# MCU.net
KiCad netlist of a schematic drawn in Altium Designer
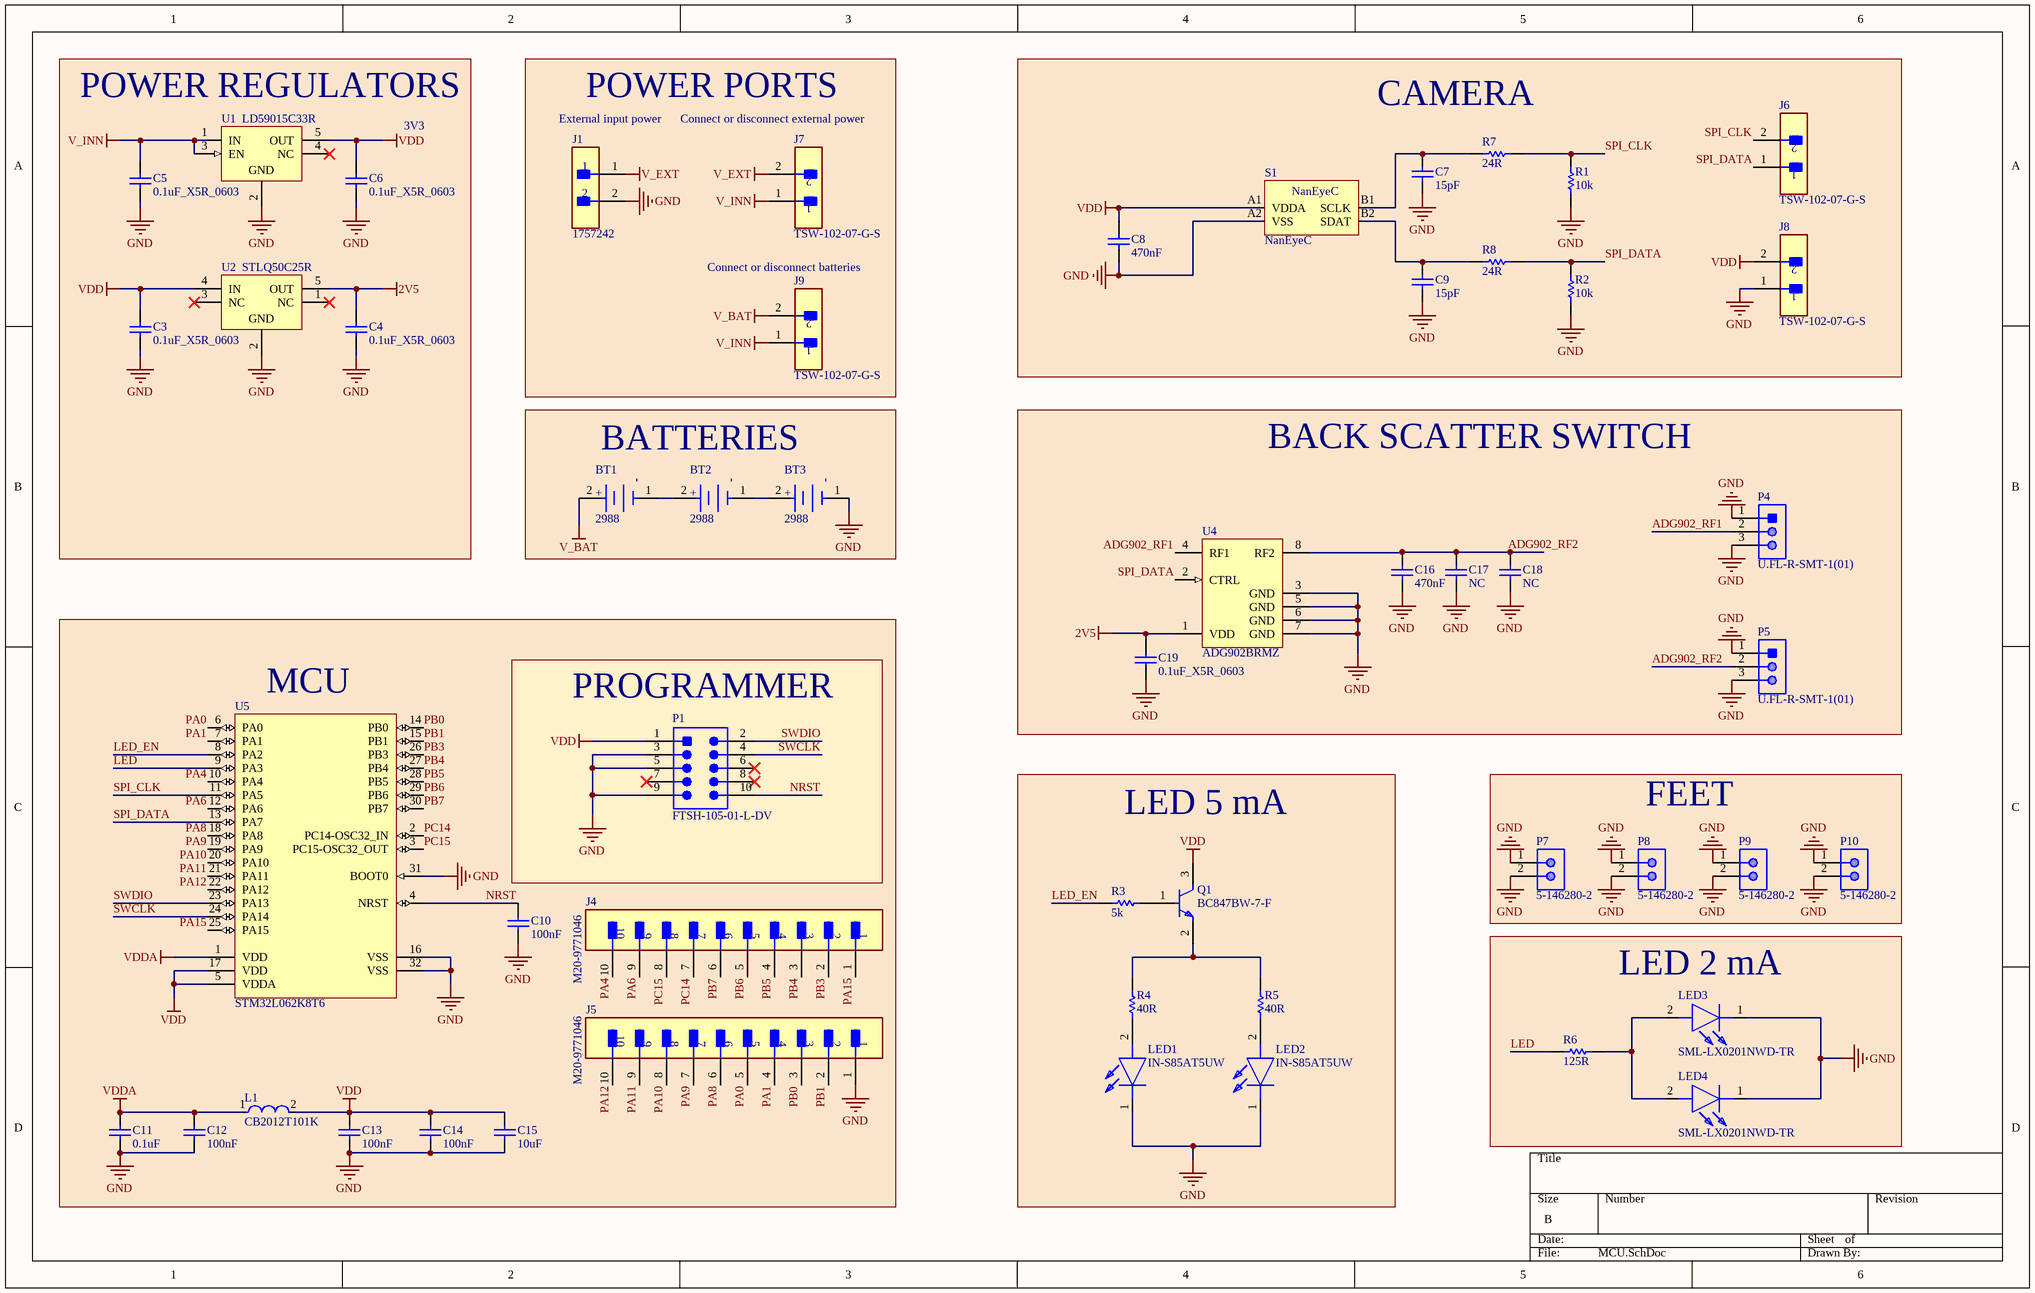
[diagram p0: MCU.SchDoc]

(export (version "E")
  (design (tool "Eeschema 10.0.6"))
  (components
    (comp (ref "BT1")
      (value "2988")
      (footprint "FP-2988-MFG")
      (description "BATTERY RETAINER COIN 7.9MM SMD")
      (libsource (lib "Altium Content Vault") (part "60d3b5b901a8747834971d0eb8cf3fd"))
    )
    (comp (ref "BT2")
      (value "2988")
      (footprint "FP-2988-MFG")
      (description "BATTERY RETAINER COIN 7.9MM SMD")
      (libsource (lib "Altium Content Vault") (part "60d3b5b901a8747834971d0eb8cf3fd"))
    )
    (comp (ref "BT3")
      (value "2988")
      (footprint "FP-2988-MFG")
      (description "BATTERY RETAINER COIN 7.9MM SMD")
      (libsource (lib "Altium Content Vault") (part "60d3b5b901a8747834971d0eb8cf3fd"))
    )
    (comp (ref "C3")
      (value "0.1uF_X5R_0603")
      (footprint "CAPC1608X90X35NL15T15")
      (fields
        (field (name "MANUFACTURER") "AVX Interconnect / Elco")
        (field (name "PART NUMBER") "06035D104KAT2A")
      )
      (libsource (lib "Altium Content Vault") (part "CAP"))
    )
    (comp (ref "C4")
      (value "0.1uF_X5R_0603")
      (footprint "CAPC1608X90X35NL15T15")
      (fields
        (field (name "MANUFACTURER") "AVX Interconnect / Elco")
        (field (name "PART NUMBER") "06035D104KAT2A")
      )
      (libsource (lib "Altium Content Vault") (part "CAP"))
    )
    (comp (ref "C5")
      (value "0.1uF_X5R_0603")
      (footprint "CAPC1608X90X35NL15T15")
      (fields
        (field (name "MANUFACTURER") "AVX Interconnect / Elco")
        (field (name "PART NUMBER") "06035D104KAT2A")
      )
      (libsource (lib "Altium Content Vault") (part "CAP"))
    )
    (comp (ref "C6")
      (value "0.1uF_X5R_0603")
      (footprint "CAPC1608X90X35NL15T15")
      (fields
        (field (name "MANUFACTURER") "AVX Interconnect / Elco")
        (field (name "PART NUMBER") "06035D104KAT2A")
      )
      (libsource (lib "Altium Content Vault") (part "CAP"))
    )
    (comp (ref "C7")
      (value "15pF")
      (footprint "CAPC1608X90X35NL15T15")
      (fields
        (field (name "MANUFACTURER") "AVX Interconnect / Elco")
        (field (name "PART NUMBER") "06035D104KAT2A")
      )
      (libsource (lib "Altium Content Vault") (part "CAP"))
    )
    (comp (ref "C8")
      (value "470nF")
      (footprint "CAPC1608X90X35NL15T15")
      (fields
        (field (name "MANUFACTURER") "AVX Interconnect / Elco")
        (field (name "PART NUMBER") "06035D104KAT2A")
      )
      (libsource (lib "Altium Content Vault") (part "CAP"))
    )
    (comp (ref "C9")
      (value "15pF")
      (footprint "CAPC1608X90X35NL15T15")
      (fields
        (field (name "MANUFACTURER") "AVX Interconnect / Elco")
        (field (name "PART NUMBER") "06035D104KAT2A")
      )
      (libsource (lib "Altium Content Vault") (part "CAP"))
    )
    (comp (ref "C10")
      (value "100nF")
      (footprint "CAPC1608X90X35NL15T15")
      (fields
        (field (name "MANUFACTURER") "AVX Interconnect / Elco")
        (field (name "PART NUMBER") "06035D104KAT2A")
      )
      (libsource (lib "Altium Content Vault") (part "CAP"))
    )
    (comp (ref "C11")
      (value "0.1uF")
      (footprint "CAPC1608X90X35NL15T15")
      (fields
        (field (name "MANUFACTURER") "AVX Interconnect / Elco")
        (field (name "PART NUMBER") "06035D104KAT2A")
      )
      (libsource (lib "Altium Content Vault") (part "CAP"))
    )
    (comp (ref "C12")
      (value "100nF")
      (footprint "CAPC1608X90X35NL15T15")
      (fields
        (field (name "MANUFACTURER") "AVX Interconnect / Elco")
        (field (name "PART NUMBER") "06035D104KAT2A")
      )
      (libsource (lib "Altium Content Vault") (part "CAP"))
    )
    (comp (ref "C13")
      (value "100nF")
      (footprint "CAPC1608X90X35NL15T15")
      (fields
        (field (name "MANUFACTURER") "AVX Interconnect / Elco")
        (field (name "PART NUMBER") "06035D104KAT2A")
      )
      (libsource (lib "Altium Content Vault") (part "CAP"))
    )
    (comp (ref "C14")
      (value "100nF")
      (footprint "CAPC1608X90X35NL15T15")
      (fields
        (field (name "MANUFACTURER") "AVX Interconnect / Elco")
        (field (name "PART NUMBER") "06035D104KAT2A")
      )
      (libsource (lib "Altium Content Vault") (part "CAP"))
    )
    (comp (ref "C15")
      (value "10uF")
      (footprint "CAPC1608X90X35NL15T15")
      (fields
        (field (name "MANUFACTURER") "AVX Interconnect / Elco")
        (field (name "PART NUMBER") "06035D104KAT2A")
      )
      (libsource (lib "Altium Content Vault") (part "CAP"))
    )
    (comp (ref "C16")
      (value "470nF")
      (footprint "CAPC1608X90X35NL15T15")
      (fields
        (field (name "MANUFACTURER") "AVX Interconnect / Elco")
        (field (name "PART NUMBER") "06035D104KAT2A")
      )
      (libsource (lib "Altium Content Vault") (part "CAP"))
    )
    (comp (ref "C17")
      (value "NC")
      (footprint "CAPC1608X90X35NL15T15")
      (fields
        (field (name "MANUFACTURER") "AVX Interconnect / Elco")
        (field (name "PART NUMBER") "06035D104KAT2A")
      )
      (libsource (lib "Altium Content Vault") (part "CAP"))
    )
    (comp (ref "C18")
      (value "NC")
      (footprint "CAPC1608X90X35NL15T15")
      (fields
        (field (name "MANUFACTURER") "AVX Interconnect / Elco")
        (field (name "PART NUMBER") "06035D104KAT2A")
      )
      (libsource (lib "Altium Content Vault") (part "CAP"))
    )
    (comp (ref "C19")
      (value "0.1uF_X5R_0603")
      (footprint "CAPC1608X90X35NL15T15")
      (fields
        (field (name "MANUFACTURER") "AVX Interconnect / Elco")
        (field (name "PART NUMBER") "06035D104KAT2A")
      )
      (libsource (lib "Altium Content Vault") (part "CAP"))
    )
    (comp (ref "J1")
      (value "1757242")
      (footprint "FP-1757242-MFG")
      (description "TERM BLOCK HDR 2POS 90DEG 5.08MM")
      (fields (field (name "VOLTAGE") "300V"))
      (libsource (lib "Altium Content Vault") (part "3bc925449376181038e59eaffc5286c"))
    )
    (comp (ref "J4")
      (value "M20-9771046")
      (footprint "FP-M20-9771046-MFG")
      (description "CONN HEADER VERT 10POS 2.54MM")
      (libsource (lib "Altium Content Vault") (part "aee40dc8b284c03a16094555aa210be"))
    )
    (comp (ref "J5")
      (value "M20-9771046")
      (footprint "FP-M20-9771046-MFG")
      (description "CONN HEADER VERT 10POS 2.54MM")
      (libsource (lib "Altium Content Vault") (part "aee40dc8b284c03a16094555aa210be"))
    )
    (comp (ref "J6")
      (value "TSW-102-07-G-S")
      (footprint "FP-TSW-102-07-G-S-MFG")
      (description "CONN HEADER VERT 2POS 2.54MM")
      (fields
        (field (name "MANUFACTURER") "Samtec")
        (field (name "OCTOPART") "https://octopart.com/tsw-102-07-g-s-samtec-272197")
      )
      (libsource (lib "") (part "3bc925449376181038e59eaffc5286c_1"))
    )
    (comp (ref "J7")
      (value "TSW-102-07-G-S")
      (footprint "FP-TSW-102-07-G-S-MFG")
      (description "CONN HEADER VERT 2POS 2.54MM")
      (fields
        (field (name "MANUFACTURER") "Samtec")
        (field (name "OCTOPART") "https://octopart.com/tsw-102-07-g-s-samtec-272197")
      )
      (libsource (lib "") (part "3bc925449376181038e59eaffc5286c_1"))
    )
    (comp (ref "J8")
      (value "TSW-102-07-G-S")
      (footprint "FP-TSW-102-07-G-S-MFG")
      (description "CONN HEADER VERT 2POS 2.54MM")
      (fields
        (field (name "MANUFACTURER") "Samtec")
        (field (name "OCTOPART") "https://octopart.com/tsw-102-07-g-s-samtec-272197")
      )
      (libsource (lib "") (part "3bc925449376181038e59eaffc5286c_1"))
    )
    (comp (ref "J9")
      (value "TSW-102-07-G-S")
      (footprint "FP-TSW-102-07-G-S-MFG")
      (description "CONN HEADER VERT 2POS 2.54MM")
      (fields
        (field (name "MANUFACTURER") "Samtec")
        (field (name "OCTOPART") "https://octopart.com/tsw-102-07-g-s-samtec-272197")
      )
      (libsource (lib "") (part "3bc925449376181038e59eaffc5286c_1"))
    )
    (comp (ref "L1")
      (value "CB2012T101K")
      (footprint "FP-CB2012-MFG")
      (description "SMD Inductors 100uH ±10% 0.13A 9.1Ω 0805")
      (fields (field (name "TOLERANCE") "10%"))
      (libsource (lib "Altium Content Vault") (part "725321dda6339637d4d059423bc1c3c"))
    )
    (comp (ref "LED1")
      (value "IN-S85AT5UW")
      (footprint "SamacSys:INS85AT5UW")
      (description "LED")
      (fields (field (name "MOUSER PART NUMBER") "743-IN-S85AT5UW"))
      (libsource (lib "*") (part "IN-S85AT5UW"))
    )
    (comp (ref "LED2")
      (value "IN-S85AT5UW")
      (footprint "SamacSys:INS85AT5UW")
      (description "LED")
      (fields (field (name "MOUSER PART NUMBER") "743-IN-S85AT5UW"))
      (libsource (lib "SamacSys") (part "IN-S85AT5UW"))
    )
    (comp (ref "LED3")
      (value "SML-LX0201NWD-TR")
      (footprint "SamacSys:LEDC0604X46N")
      (description "LED")
      (fields (field (name "MOUSER2 PART NUMBER") "696-SMLLX0201NWDTR"))
      (libsource (lib "*") (part "SML-LX0201NWD-TR"))
    )
    (comp (ref "LED4")
      (value "SML-LX0201NWD-TR")
      (footprint "SamacSys:LEDC0604X46N")
      (description "LED")
      (fields (field (name "MOUSER2 PART NUMBER") "696-SMLLX0201NWDTR"))
      (libsource (lib "*") (part "SML-LX0201NWD-TR"))
    )
    (comp (ref "P1")
      (value "FTSH-105-01-L-DV")
      (footprint "SMTC-FTSH-105-01-L-DV_V")
      (description "Male Header, Pitch 1.27 mm, 2 x 5 Position, Height 5.96 mm, -55 to 125 degC, RoHS, Bulk")
      (fields (field (name "MANUFACTURER") "Samtec"))
      (libsource (lib "Altium Content Vault") (part "CN-2P-M-R10"))
    )
    (comp (ref "P4")
      (value "U.FL-R-SMT-1(01)")
      (footprint "HRS-U.FL-R-SMT-3_V")
      (description "Ultra Small Coaxial Connector, 6 GHz, -40 to 90 degC, 3-Pin SMD, RoHS, Bulk")
      (fields (field (name "MANUFACTURER") "Hirose Electric"))
      (libsource (lib "Altium Content Vault") (part "CN-1P-M-R3"))
    )
    (comp (ref "P5")
      (value "U.FL-R-SMT-1(01)")
      (footprint "HRS-U.FL-R-SMT-3_V")
      (description "Ultra Small Coaxial Connector, 6 GHz, -40 to 90 degC, 3-Pin SMD, RoHS, Bulk")
      (fields (field (name "MANUFACTURER") "Hirose Electric"))
      (libsource (lib "Altium Content Vault") (part "CN-1P-M-R3"))
    )
    (comp (ref "P7")
      (value "5-146280-2")
      (footprint "TECO-5-146280-2_V")
      (fields (field (name "MANUFACTURER") "TE Connectivity"))
      (libsource (lib "Altium Content Vault") (part "CN-1P-M-R2"))
    )
    (comp (ref "P8")
      (value "5-146280-2")
      (footprint "TECO-5-146280-2_V")
      (fields (field (name "MANUFACTURER") "TE Connectivity"))
      (libsource (lib "Altium Content Vault") (part "CN-1P-M-R2"))
    )
    (comp (ref "P9")
      (value "5-146280-2")
      (footprint "TECO-5-146280-2_V")
      (fields (field (name "MANUFACTURER") "TE Connectivity"))
      (libsource (lib "Altium Content Vault") (part "CN-1P-M-R2"))
    )
    (comp (ref "P10")
      (value "5-146280-2")
      (footprint "TECO-5-146280-2_V")
      (fields (field (name "MANUFACTURER") "TE Connectivity"))
      (libsource (lib "Altium Content Vault") (part "CN-1P-M-R2"))
    )
    (comp (ref "Q1")
      (value "BC847BW-7-F")
      (footprint "FP-SOT323-MFG")
      (description "TRANS NPN 45V 0.1A SC70-3")
      (fields
        (field (name "OCTOPART") "https://octopart.com/bc847bw-7-f-diodes+inc.-354380")
        (field (name "MANUFACTURER") "Diodes Inc")
      )
      (libsource (lib "Altium Content Vault") (part "b44e953556f554d0102664c7d152cb4"))
    )
    (comp (ref "R1")
      (value "10k")
      (footprint "RESC1608X50X30ML20T20")
      (fields (field (name "PART NUMBER") "RR0816P-4640-D-65A") (field (name "MANUFACTURER") "Susumu"))
      (libsource (lib "Altium Content Vault") (part "RES"))
    )
    (comp (ref "R2")
      (value "10k")
      (footprint "RESC1608X50X30ML20T20")
      (fields (field (name "PART NUMBER") "RR0816P-4640-D-65A") (field (name "MANUFACTURER") "Susumu"))
      (libsource (lib "Altium Content Vault") (part "RES"))
    )
    (comp (ref "R3")
      (value "5k")
      (footprint "RESC1608X50X30ML20T20")
      (fields (field (name "PART NUMBER") "RR0816P-4640-D-65A") (field (name "MANUFACTURER") "Susumu"))
      (libsource (lib "Altium Content Vault") (part "RES"))
    )
    (comp (ref "R4")
      (value "40R")
      (footprint "RESC1608X50X30ML20T20")
      (fields (field (name "PART NUMBER") "RR0816P-4640-D-65A") (field (name "MANUFACTURER") "Susumu"))
      (libsource (lib "Altium Content Vault") (part "RES"))
    )
    (comp (ref "R5")
      (value "40R")
      (footprint "RESC1608X50X30ML20T20")
      (fields (field (name "PART NUMBER") "RR0816P-4640-D-65A") (field (name "MANUFACTURER") "Susumu"))
      (libsource (lib "Altium Content Vault") (part "RES"))
    )
    (comp (ref "R6")
      (value "125R")
      (footprint "RESC1608X50X30ML20T20")
      (fields (field (name "PART NUMBER") "RR0816P-4640-D-65A") (field (name "MANUFACTURER") "Susumu"))
      (libsource (lib "Altium Content Vault") (part "RES"))
    )
    (comp (ref "R7")
      (value "24R")
      (footprint "RESC1608X50X30ML20T20")
      (fields (field (name "PART NUMBER") "RR0816P-4640-D-65A") (field (name "MANUFACTURER") "Susumu"))
      (libsource (lib "Altium Content Vault") (part "RES"))
    )
    (comp (ref "R8")
      (value "24R")
      (footprint "RESC1608X50X30ML20T20")
      (fields (field (name "PART NUMBER") "RR0816P-4640-D-65A") (field (name "MANUFACTURER") "Susumu"))
      (libsource (lib "Altium Content Vault") (part "RES"))
    )
    (comp (ref "S1")
      (value "NanEyeC")
      (footprint "NanEyeC")
      (description "Camera module NanEyeC from AMS. The Part will be delivered by us")
      (libsource (lib "WCE_thesis") (part "NanEyeC"))
    )
    (comp (ref "U1")
      (value "LD59015C33R")
      (footprint "SOT323-5L-L036_L")
      (description "150 mA Low Noise High PSRR linear Voltage Regulator, 3.3V, 5-Pin SOT-323, Tape and Reel")
      (libsource (lib "Altium Content Vault") (part "PM-REG-LD39015M-SOT5"))
    )
    (comp (ref "U2")
      (value "STLQ50C25R")
      (footprint "SOT323-5L_L")
      (description "50mA, 3µA Supply Current Low Drop Linear Regulator, 2.5V, 5-Pin SOT-323, Tape and Reel")
      (libsource (lib "Altium Content Vault") (part "PM-REG-STLQ50C-SOT5"))
    )
    (comp (ref "U4")
      (value "ADG902BRMZ")
      (footprint "ADI-RM-8_L")
      (libsource (lib "Altium Content Vault") (part "ADI-ADG902-RM-8"))
    )
    (comp (ref "U5")
      (value "STM32L062K8T6")
      (footprint "STM-LQFP32_M")
      (libsource (lib "Altium Content Vault") (part "MC-ARM-STM32L062-LQFP32"))
    )
  )
  (nets
    (net (code "2") (name "/ADG902_RF1") (class "Default")
      (node (ref "P4") (pin "2") (pinfunction "2_2") (pintype "passive"))
      (node (ref "U4") (pin "4") (pinfunction "RF1_4") (pintype "passive"))
    )
    (net (code "3") (name "/ADG902_RF2") (class "Default")
      (node (ref "C16") (pin "2") (pinfunction "2_2") (pintype "passive"))
      (node (ref "C17") (pin "2") (pinfunction "2_2") (pintype "passive"))
      (node (ref "C18") (pin "2") (pinfunction "2_2") (pintype "passive"))
      (node (ref "P5") (pin "2") (pinfunction "2_2") (pintype "passive"))
      (node (ref "U4") (pin "8") (pinfunction "RF2_8") (pintype "passive"))
    )
    (net (code "4") (name "/LED") (class "Default")
      (node (ref "R6") (pin "2") (pinfunction "2_2") (pintype "passive"))
      (node (ref "U5") (pin "9") (pinfunction "PA3_9") (pintype "bidirectional"))
    )
    (net (code "5") (name "/LED_EN") (class "Default")
      (node (ref "R3") (pin "2") (pinfunction "2_2") (pintype "passive"))
      (node (ref "U5") (pin "8") (pinfunction "PA2_8") (pintype "bidirectional"))
    )
    (net (code "6") (name "/NRST") (class "Default")
      (node (ref "C10") (pin "2") (pinfunction "2_2") (pintype "passive"))
      (node (ref "P1") (pin "10") (pinfunction "10_10") (pintype "passive"))
      (node (ref "U5") (pin "4") (pinfunction "NRST_4") (pintype "bidirectional"))
    )
    (net (code "7") (name "/PA0") (class "Default")
      (node (ref "J5") (pin "5") (pinfunction "5_5") (pintype "passive"))
      (node (ref "U5") (pin "6") (pinfunction "PA0_6") (pintype "bidirectional"))
    )
    (net (code "8") (name "/PA1") (class "Default")
      (node (ref "J5") (pin "4") (pinfunction "4_4") (pintype "passive"))
      (node (ref "U5") (pin "7") (pinfunction "PA1_7") (pintype "bidirectional"))
    )
    (net (code "9") (name "/PA4") (class "Default")
      (node (ref "J4") (pin "10") (pinfunction "10_10") (pintype "passive"))
      (node (ref "U5") (pin "10") (pinfunction "PA4_10") (pintype "bidirectional"))
    )
    (net (code "10") (name "/PA6") (class "Default")
      (node (ref "J4") (pin "9") (pinfunction "9_9") (pintype "passive"))
      (node (ref "U5") (pin "12") (pinfunction "PA6_12") (pintype "bidirectional"))
    )
    (net (code "11") (name "/PA8") (class "Default")
      (node (ref "J5") (pin "6") (pinfunction "6_6") (pintype "passive"))
      (node (ref "U5") (pin "18") (pinfunction "PA8_18") (pintype "bidirectional"))
    )
    (net (code "12") (name "/PA9") (class "Default")
      (node (ref "J5") (pin "7") (pinfunction "7_7") (pintype "passive"))
      (node (ref "U5") (pin "19") (pinfunction "PA9_19") (pintype "bidirectional"))
    )
    (net (code "13") (name "/PA10") (class "Default")
      (node (ref "J5") (pin "8") (pinfunction "8_8") (pintype "passive"))
      (node (ref "U5") (pin "20") (pinfunction "PA10_20") (pintype "bidirectional"))
    )
    (net (code "14") (name "/PA11") (class "Default")
      (node (ref "J5") (pin "9") (pinfunction "9_9") (pintype "passive"))
      (node (ref "U5") (pin "21") (pinfunction "PA11_21") (pintype "bidirectional"))
    )
    (net (code "15") (name "/PA12") (class "Default")
      (node (ref "J5") (pin "10") (pinfunction "10_10") (pintype "passive"))
      (node (ref "U5") (pin "22") (pinfunction "PA12_22") (pintype "bidirectional"))
    )
    (net (code "16") (name "/PA15") (class "Default")
      (node (ref "J4") (pin "1") (pinfunction "1_1") (pintype "passive"))
      (node (ref "U5") (pin "25") (pinfunction "PA15_25") (pintype "bidirectional"))
    )
    (net (code "17") (name "/PB0") (class "Default")
      (node (ref "J5") (pin "3") (pinfunction "3_3") (pintype "passive"))
      (node (ref "U5") (pin "14") (pinfunction "PB0_14") (pintype "bidirectional"))
    )
    (net (code "18") (name "/PB1") (class "Default")
      (node (ref "J5") (pin "2") (pinfunction "2_2") (pintype "passive"))
      (node (ref "U5") (pin "15") (pinfunction "PB1_15") (pintype "bidirectional"))
    )
    (net (code "19") (name "/PB3") (class "Default")
      (node (ref "J4") (pin "2") (pinfunction "2_2") (pintype "passive"))
      (node (ref "U5") (pin "26") (pinfunction "PB3_26") (pintype "bidirectional"))
    )
    (net (code "20") (name "/PB4") (class "Default")
      (node (ref "J4") (pin "3") (pinfunction "3_3") (pintype "passive"))
      (node (ref "U5") (pin "27") (pinfunction "PB4_27") (pintype "bidirectional"))
    )
    (net (code "21") (name "/PB5") (class "Default")
      (node (ref "J4") (pin "4") (pinfunction "4_4") (pintype "passive"))
      (node (ref "U5") (pin "28") (pinfunction "PB5_28") (pintype "bidirectional"))
    )
    (net (code "22") (name "/PB6") (class "Default")
      (node (ref "J4") (pin "5") (pinfunction "5_5") (pintype "passive"))
      (node (ref "U5") (pin "29") (pinfunction "PB6_29") (pintype "bidirectional"))
    )
    (net (code "23") (name "/PB7") (class "Default")
      (node (ref "J4") (pin "6") (pinfunction "6_6") (pintype "passive"))
      (node (ref "U5") (pin "30") (pinfunction "PB7_30") (pintype "bidirectional"))
    )
    (net (code "24") (name "/PC14") (class "Default")
      (node (ref "J4") (pin "7") (pinfunction "7_7") (pintype "passive"))
      (node (ref "U5") (pin "2") (pinfunction "PC14-OSC32_IN_2") (pintype "bidirectional"))
    )
    (net (code "25") (name "/PC15") (class "Default")
      (node (ref "J4") (pin "8") (pinfunction "8_8") (pintype "passive"))
      (node (ref "U5") (pin "3") (pinfunction "PC15-OSC32_OUT_3") (pintype "bidirectional"))
    )
    (net (code "26") (name "/SPI_CLK") (class "Default")
      (node (ref "J6") (pin "2") (pinfunction "2_2") (pintype "passive"))
      (node (ref "R1") (pin "2") (pinfunction "2_2") (pintype "passive"))
      (node (ref "R7") (pin "1") (pinfunction "1_1") (pintype "passive"))
      (node (ref "U5") (pin "11") (pinfunction "PA5_11") (pintype "bidirectional"))
    )
    (net (code "27") (name "/SPI_DATA") (class "Default")
      (node (ref "J6") (pin "1") (pinfunction "1_1") (pintype "passive"))
      (node (ref "R2") (pin "2") (pinfunction "2_2") (pintype "passive"))
      (node (ref "R8") (pin "1") (pinfunction "1_1") (pintype "passive"))
      (node (ref "U4") (pin "2") (pinfunction "CTRL_2") (pintype "input"))
      (node (ref "U5") (pin "13") (pinfunction "PA7_13") (pintype "bidirectional"))
    )
    (net (code "28") (name "/SWCLK") (class "Default")
      (node (ref "P1") (pin "4") (pinfunction "4_4") (pintype "passive"))
      (node (ref "U5") (pin "24") (pinfunction "PA14_24") (pintype "bidirectional"))
    )
    (net (code "29") (name "/SWDIO") (class "Default")
      (node (ref "P1") (pin "2") (pinfunction "2_2") (pintype "passive"))
      (node (ref "U5") (pin "23") (pinfunction "PA13_23") (pintype "bidirectional"))
    )
    (net (code "30") (name "2V5") (class "Default")
      (node (ref "C19") (pin "2") (pinfunction "2_2") (pintype "passive"))
      (node (ref "C4") (pin "2") (pinfunction "2_2") (pintype "passive"))
      (node (ref "U2") (pin "5") (pinfunction "OUT_5") (pintype "power_in"))
      (node (ref "U4") (pin "1") (pinfunction "VDD_1") (pintype "power_in"))
    )
    (net (code "31") (name "GND") (class "Default")
      (node (ref "BT3") (pin "1") (pinfunction "C_1") (pintype "passive"))
      (node (ref "C10") (pin "1") (pinfunction "1_1") (pintype "passive"))
      (node (ref "C11") (pin "1") (pinfunction "1_1") (pintype "passive"))
      (node (ref "C12") (pin "1") (pinfunction "1_1") (pintype "passive"))
      (node (ref "C13") (pin "1") (pinfunction "1_1") (pintype "passive"))
      (node (ref "C14") (pin "1") (pinfunction "1_1") (pintype "passive"))
      (node (ref "C15") (pin "1") (pinfunction "1_1") (pintype "passive"))
      (node (ref "C16") (pin "1") (pinfunction "1_1") (pintype "passive"))
      (node (ref "C17") (pin "1") (pinfunction "1_1") (pintype "passive"))
      (node (ref "C18") (pin "1") (pinfunction "1_1") (pintype "passive"))
      (node (ref "C19") (pin "1") (pinfunction "1_1") (pintype "passive"))
      (node (ref "C3") (pin "1") (pinfunction "1_1") (pintype "passive"))
      (node (ref "C4") (pin "1") (pinfunction "1_1") (pintype "passive"))
      (node (ref "C5") (pin "1") (pinfunction "1_1") (pintype "passive"))
      (node (ref "C6") (pin "1") (pinfunction "1_1") (pintype "passive"))
      (node (ref "C7") (pin "1") (pinfunction "1_1") (pintype "passive"))
      (node (ref "C8") (pin "1") (pinfunction "1_1") (pintype "passive"))
      (node (ref "C9") (pin "1") (pinfunction "1_1") (pintype "passive"))
      (node (ref "J1") (pin "2") (pinfunction "2_2") (pintype "passive"))
      (node (ref "J5") (pin "1") (pinfunction "1_1") (pintype "passive"))
      (node (ref "J8") (pin "1") (pinfunction "1_1") (pintype "passive"))
      (node (ref "LED1") (pin "1") (pinfunction "K_1") (pintype "passive"))
      (node (ref "LED2") (pin "1") (pinfunction "K_1") (pintype "passive"))
      (node (ref "LED3") (pin "1") (pinfunction "K_1") (pintype "passive"))
      (node (ref "LED4") (pin "1") (pinfunction "K_1") (pintype "passive"))
      (node (ref "P1") (pin "3") (pinfunction "3_3") (pintype "passive"))
      (node (ref "P1") (pin "5") (pinfunction "5_5") (pintype "passive"))
      (node (ref "P1") (pin "9") (pinfunction "9_9") (pintype "passive"))
      (node (ref "P10") (pin "1") (pinfunction "1_1") (pintype "passive"))
      (node (ref "P10") (pin "2") (pinfunction "2_2") (pintype "passive"))
      (node (ref "P4") (pin "1") (pinfunction "1_1") (pintype "passive"))
      (node (ref "P4") (pin "3") (pinfunction "3_3") (pintype "passive"))
      (node (ref "P5") (pin "1") (pinfunction "1_1") (pintype "passive"))
      (node (ref "P5") (pin "3") (pinfunction "3_3") (pintype "passive"))
      (node (ref "P7") (pin "1") (pinfunction "1_1") (pintype "passive"))
      (node (ref "P7") (pin "2") (pinfunction "2_2") (pintype "passive"))
      (node (ref "P8") (pin "1") (pinfunction "1_1") (pintype "passive"))
      (node (ref "P8") (pin "2") (pinfunction "2_2") (pintype "passive"))
      (node (ref "P9") (pin "1") (pinfunction "1_1") (pintype "passive"))
      (node (ref "P9") (pin "2") (pinfunction "2_2") (pintype "passive"))
      (node (ref "R1") (pin "1") (pinfunction "1_1") (pintype "passive"))
      (node (ref "R2") (pin "1") (pinfunction "1_1") (pintype "passive"))
      (node (ref "S1") (pin "A2") (pinfunction "VSS_A2") (pintype "passive"))
      (node (ref "U1") (pin "2") (pinfunction "GND_2") (pintype "power_in"))
      (node (ref "U2") (pin "2") (pinfunction "GND_2") (pintype "power_in"))
      (node (ref "U4") (pin "3") (pinfunction "GND_3") (pintype "power_in"))
      (node (ref "U4") (pin "5") (pinfunction "GND_5") (pintype "power_in"))
      (node (ref "U4") (pin "6") (pinfunction "GND_6") (pintype "power_in"))
      (node (ref "U4") (pin "7") (pinfunction "GND_7") (pintype "power_in"))
      (node (ref "U5") (pin "16") (pinfunction "VSS_16") (pintype "power_in"))
      (node (ref "U5") (pin "31") (pinfunction "BOOT0_31") (pintype "input"))
      (node (ref "U5") (pin "32") (pinfunction "VSS_32") (pintype "power_in"))
    )
    (net (code "32") (name "Net-(BT1-C)") (class "Default")
      (node (ref "BT1") (pin "1") (pinfunction "C_1") (pintype "passive"))
      (node (ref "BT2") (pin "2") (pinfunction "A_2") (pintype "passive"))
    )
    (net (code "33") (name "Net-(BT2-C)") (class "Default")
      (node (ref "BT2") (pin "1") (pinfunction "C_1") (pintype "passive"))
      (node (ref "BT3") (pin "2") (pinfunction "A_2") (pintype "passive"))
    )
    (net (code "34") (name "Net-(LED1-A)") (class "Default")
      (node (ref "LED1") (pin "2") (pinfunction "A_2") (pintype "passive"))
      (node (ref "R4") (pin "1") (pinfunction "1_1") (pintype "passive"))
    )
    (net (code "35") (name "Net-(LED2-A)") (class "Default")
      (node (ref "LED2") (pin "2") (pinfunction "A_2") (pintype "passive"))
      (node (ref "R5") (pin "1") (pinfunction "1_1") (pintype "passive"))
    )
    (net (code "36") (name "Net-(LED3-A)") (class "Default")
      (node (ref "LED3") (pin "2") (pinfunction "A_2") (pintype "passive"))
      (node (ref "LED4") (pin "2") (pinfunction "A_2") (pintype "passive"))
      (node (ref "R6") (pin "1") (pinfunction "1_1") (pintype "passive"))
    )
    (net (code "37") (name "Net-(Q1-B)") (class "Default")
      (node (ref "Q1") (pin "1") (pinfunction "B_1") (pintype "passive"))
      (node (ref "R3") (pin "1") (pinfunction "1_1") (pintype "passive"))
    )
    (net (code "38") (name "Net-(Q1-E)") (class "Default")
      (node (ref "Q1") (pin "2") (pinfunction "E_2") (pintype "passive"))
      (node (ref "R4") (pin "2") (pinfunction "2_2") (pintype "passive"))
      (node (ref "R5") (pin "2") (pinfunction "2_2") (pintype "passive"))
    )
    (net (code "39") (name "Net-(S1-SCLK)") (class "Default")
      (node (ref "C7") (pin "2") (pinfunction "2_2") (pintype "passive"))
      (node (ref "R7") (pin "2") (pinfunction "2_2") (pintype "passive"))
      (node (ref "S1") (pin "B1") (pinfunction "SCLK_B1") (pintype "power_in"))
    )
    (net (code "40") (name "Net-(S1-SDAT)") (class "Default")
      (node (ref "C9") (pin "2") (pinfunction "2_2") (pintype "passive"))
      (node (ref "R8") (pin "2") (pinfunction "2_2") (pintype "passive"))
      (node (ref "S1") (pin "B2") (pinfunction "SDAT_B2") (pintype "passive"))
    )
    (net (code "41") (name "VDD") (class "Default")
      (node (ref "C13") (pin "2") (pinfunction "2_2") (pintype "passive"))
      (node (ref "C14") (pin "2") (pinfunction "2_2") (pintype "passive"))
      (node (ref "C15") (pin "2") (pinfunction "2_2") (pintype "passive"))
      (node (ref "C3") (pin "2") (pinfunction "2_2") (pintype "passive"))
      (node (ref "C6") (pin "2") (pinfunction "2_2") (pintype "passive"))
      (node (ref "C8") (pin "2") (pinfunction "2_2") (pintype "passive"))
      (node (ref "J8") (pin "2") (pinfunction "2_2") (pintype "passive"))
      (node (ref "L1") (pin "2") (pinfunction "2_2") (pintype "passive"))
      (node (ref "P1") (pin "1") (pinfunction "1_1") (pintype "passive"))
      (node (ref "Q1") (pin "3") (pinfunction "C_3") (pintype "passive"))
      (node (ref "S1") (pin "A1") (pinfunction "VDDA_A1") (pintype "power_in"))
      (node (ref "U1") (pin "5") (pinfunction "OUT_5") (pintype "power_in"))
      (node (ref "U2") (pin "4") (pinfunction "IN_4") (pintype "power_in"))
      (node (ref "U5") (pin "17") (pinfunction "VDD_17") (pintype "power_in"))
      (node (ref "U5") (pin "5") (pinfunction "VDDA_5") (pintype "power_in"))
    )
    (net (code "42") (name "VDDA") (class "Default")
      (node (ref "C11") (pin "2") (pinfunction "2_2") (pintype "passive"))
      (node (ref "C12") (pin "2") (pinfunction "2_2") (pintype "passive"))
      (node (ref "L1") (pin "1") (pinfunction "1_1") (pintype "passive"))
      (node (ref "U5") (pin "1") (pinfunction "VDD_1") (pintype "power_in"))
    )
    (net (code "43") (name "V_BAT") (class "Default")
      (node (ref "BT1") (pin "2") (pinfunction "A_2") (pintype "passive"))
      (node (ref "J9") (pin "2") (pinfunction "2_2") (pintype "passive"))
    )
    (net (code "44") (name "V_EXT") (class "Default")
      (node (ref "J1") (pin "1") (pinfunction "1_1") (pintype "passive"))
      (node (ref "J7") (pin "2") (pinfunction "2_2") (pintype "passive"))
    )
    (net (code "45") (name "V_INN") (class "Default")
      (node (ref "C5") (pin "2") (pinfunction "2_2") (pintype "passive"))
      (node (ref "J7") (pin "1") (pinfunction "1_1") (pintype "passive"))
      (node (ref "J9") (pin "1") (pinfunction "1_1") (pintype "passive"))
      (node (ref "U1") (pin "1") (pinfunction "IN_1") (pintype "power_in"))
      (node (ref "U1") (pin "3") (pinfunction "EN_3") (pintype "input"))
    )
    (net (code "46") (name "unconnected-(P1-Pad6)") (class "Default")
      (node (ref "P1") (pin "6") (pinfunction "6_6") (pintype "passive+no_connect"))
    )
    (net (code "47") (name "unconnected-(P1-Pad7)") (class "Default")
      (node (ref "P1") (pin "7") (pinfunction "7_7") (pintype "passive+no_connect"))
    )
    (net (code "48") (name "unconnected-(P1-Pad8)") (class "Default")
      (node (ref "P1") (pin "8") (pinfunction "8_8") (pintype "passive+no_connect"))
    )
    (net (code "49") (name "unconnected-(U1-NC-Pad4)") (class "Default")
      (node (ref "U1") (pin "4") (pinfunction "NC_4") (pintype "passive+no_connect"))
    )
    (net (code "50") (name "unconnected-(U2-NC-Pad1)") (class "Default")
      (node (ref "U2") (pin "1") (pinfunction "NC_1") (pintype "passive+no_connect"))
    )
    (net (code "51") (name "unconnected-(U2-NC-Pad3)") (class "Default")
      (node (ref "U2") (pin "3") (pinfunction "NC_3") (pintype "passive+no_connect"))
    )
  )
)
